# Cabinet_System_F.net
KiCad netlist of a schematic drawn in Altium Designer
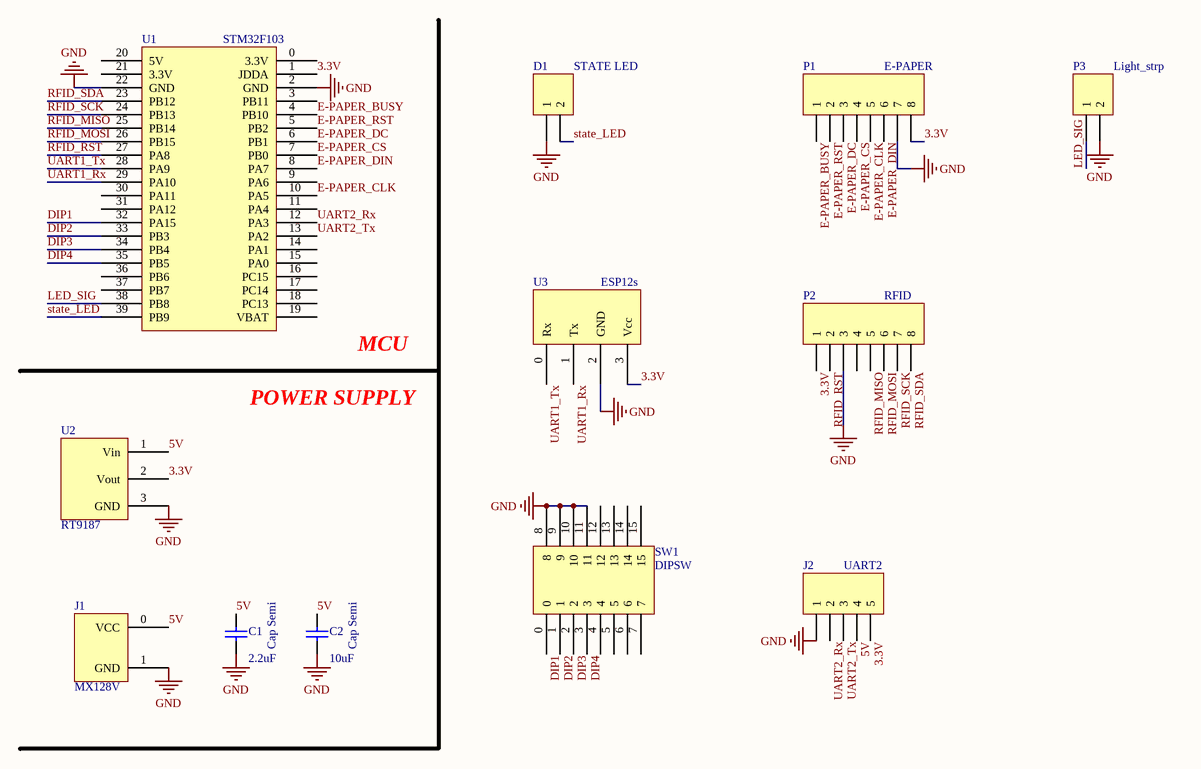
[diagram p0: Cabinet_System_F.SchDoc]

(export (version "E")
  (design (tool "Eeschema 10.0.6"))
  (components
    (comp (ref "C1")
      (value "Cap Semi")
      (footprint "1608[0603]")
      (description "Capacitor (Semiconductor SIM Model)")
      (fields (field (name "ALTIUM_VALUE") "2.2uF") (field (name "PUBLISHER") "Altium Limited"))
      (libsource (lib "Miscellaneous Devices") (part "Cap Semi"))
    )
    (comp (ref "C2")
      (value "Cap Semi")
      (footprint "1608[0603]")
      (description "Capacitor (Semiconductor SIM Model)")
      (fields (field (name "ALTIUM_VALUE") "10uF") (field (name "PUBLISHER") "Altium Limited"))
      (libsource (lib "Miscellaneous Devices") (part "Cap Semi"))
    )
    (comp (ref "D1")
      (value "STATE LED")
      (footprint "HDR1X2")
      (description "Header, 2-Pin")
      (fields (field (name "PUBLISHER") "Altium Limited"))
      (libsource (lib "Miscellaneous Connectors") (part "Header 2"))
    )
    (comp (ref "J1") (value "MX128V") (footprint "MX128V") (libsource (lib "cabinet_LIB") (part "MX128V")))
    (comp (ref "J2")
      (value "UART2")
      (footprint "HDR1X5")
      (description "Header, 5-Pin")
      (fields (field (name "PUBLISHER") "Altium Limited"))
      (libsource (lib "Miscellaneous Connectors") (part "Header 5"))
    )
    (comp (ref "P1")
      (value "E-PAPER")
      (footprint "HDR1X8")
      (description "Header, 8-Pin")
      (fields (field (name "PUBLISHER") "Altium Limited"))
      (libsource (lib "Miscellaneous Connectors") (part "Header 8"))
    )
    (comp (ref "P2")
      (value "RFID")
      (footprint "HDR1X8")
      (description "Header, 8-Pin")
      (fields (field (name "PUBLISHER") "Altium Limited"))
      (libsource (lib "Miscellaneous Connectors") (part "Header 8"))
    )
    (comp (ref "P3")
      (value "Light_strp")
      (footprint "HDR1X2")
      (description "Header, 2-Pin")
      (fields (field (name "PUBLISHER") "Altium Limited"))
      (libsource (lib "Miscellaneous Connectors") (part "Header 2"))
    )
    (comp (ref "SW1") (value "DIPSW") (footprint "DIPSW") (libsource (lib "cabinet_LIB") (part "DIPSW")))
    (comp (ref "U1")
      (value "STM32F103")
      (footprint "STM32F103")
      (libsource (lib "cabinet_LIB") (part "STM32F103"))
    )
    (comp (ref "U2") (value "RT9187") (footprint "RT9187") (libsource (lib "cabinet_LIB") (part "RT9187")))
    (comp (ref "U3") (value "ESP12s") (footprint "ESP12s") (libsource (lib "cabinet_LIB") (part "ESP12s")))
  )
  (nets
    (net (code "1") (name "/3.3V") (class "Default")
      (node (ref "J2") (pin "5") (pinfunction "5_5") (pintype "passive"))
      (node (ref "P1") (pin "8") (pinfunction "8_8") (pintype "passive"))
      (node (ref "P2") (pin "1") (pinfunction "1_1") (pintype "passive"))
      (node (ref "U1") (pin "1") (pinfunction "JDDA_1") (pintype "passive"))
      (node (ref "U2") (pin "2") (pinfunction "Vout_2") (pintype "passive"))
      (node (ref "U3") (pin "3") (pinfunction "Vcc_3") (pintype "passive"))
    )
    (net (code "2") (name "/5V") (class "Default")
      (node (ref "C1") (pin "2") (pinfunction "2_2") (pintype "passive"))
      (node (ref "C2") (pin "2") (pinfunction "2_2") (pintype "passive"))
      (node (ref "J1") (pin "0") (pinfunction "VCC_0") (pintype "passive"))
      (node (ref "J2") (pin "4") (pinfunction "4_4") (pintype "passive"))
      (node (ref "U2") (pin "1") (pinfunction "Vin_1") (pintype "passive"))
    )
    (net (code "3") (name "/DIP1") (class "Default")
      (node (ref "SW1") (pin "0") (pinfunction "0_0") (pintype "passive"))
      (node (ref "U1") (pin "32") (pinfunction "PA15_32") (pintype "passive"))
    )
    (net (code "4") (name "/DIP2") (class "Default")
      (node (ref "SW1") (pin "1") (pinfunction "1_1") (pintype "passive"))
      (node (ref "U1") (pin "33") (pinfunction "PB3_33") (pintype "passive"))
    )
    (net (code "5") (name "/DIP3") (class "Default")
      (node (ref "SW1") (pin "2") (pinfunction "2_2") (pintype "passive"))
      (node (ref "U1") (pin "34") (pinfunction "PB4_34") (pintype "passive"))
    )
    (net (code "6") (name "/DIP4") (class "Default")
      (node (ref "SW1") (pin "3") (pinfunction "3_3") (pintype "passive"))
      (node (ref "U1") (pin "35") (pinfunction "PB5_35") (pintype "passive"))
    )
    (net (code "7") (name "/E-PAPER_BUSY") (class "Default")
      (node (ref "P1") (pin "1") (pinfunction "1_1") (pintype "passive"))
      (node (ref "U1") (pin "4") (pinfunction "PB10_4") (pintype "passive"))
    )
    (net (code "8") (name "/E-PAPER_CLK") (class "Default")
      (node (ref "P1") (pin "5") (pinfunction "5_5") (pintype "passive"))
      (node (ref "U1") (pin "10") (pinfunction "PA5_10") (pintype "passive"))
    )
    (net (code "9") (name "/E-PAPER_CS") (class "Default")
      (node (ref "P1") (pin "4") (pinfunction "4_4") (pintype "passive"))
      (node (ref "U1") (pin "7") (pinfunction "PB0_7") (pintype "passive"))
    )
    (net (code "10") (name "/E-PAPER_DC") (class "Default")
      (node (ref "P1") (pin "3") (pinfunction "3_3") (pintype "passive"))
      (node (ref "U1") (pin "6") (pinfunction "PB1_6") (pintype "passive"))
    )
    (net (code "11") (name "/E-PAPER_DIN") (class "Default")
      (node (ref "P1") (pin "6") (pinfunction "6_6") (pintype "passive"))
      (node (ref "U1") (pin "8") (pinfunction "PA7_8") (pintype "passive"))
    )
    (net (code "12") (name "/E-PAPER_RST") (class "Default")
      (node (ref "P1") (pin "2") (pinfunction "2_2") (pintype "passive"))
      (node (ref "U1") (pin "5") (pinfunction "PB2_5") (pintype "passive"))
    )
    (net (code "13") (name "/LED_SIG") (class "Default")
      (node (ref "P3") (pin "1") (pinfunction "1_1") (pintype "passive"))
      (node (ref "U1") (pin "38") (pinfunction "PB8_38") (pintype "passive"))
    )
    (net (code "14") (name "/RFID_MISO") (class "Default")
      (node (ref "P2") (pin "5") (pinfunction "5_5") (pintype "passive"))
      (node (ref "U1") (pin "25") (pinfunction "PB14_25") (pintype "passive"))
    )
    (net (code "15") (name "/RFID_MOSI") (class "Default")
      (node (ref "P2") (pin "6") (pinfunction "6_6") (pintype "passive"))
      (node (ref "U1") (pin "26") (pinfunction "PB15_26") (pintype "passive"))
    )
    (net (code "16") (name "/RFID_RST") (class "Default")
      (node (ref "P2") (pin "2") (pinfunction "2_2") (pintype "passive"))
      (node (ref "U1") (pin "27") (pinfunction "PA8_27") (pintype "passive"))
    )
    (net (code "17") (name "/RFID_SCK") (class "Default")
      (node (ref "P2") (pin "7") (pinfunction "7_7") (pintype "passive"))
      (node (ref "U1") (pin "24") (pinfunction "PB13_24") (pintype "passive"))
    )
    (net (code "18") (name "/RFID_SDA") (class "Default")
      (node (ref "P2") (pin "8") (pinfunction "8_8") (pintype "passive"))
      (node (ref "U1") (pin "23") (pinfunction "PB12_23") (pintype "passive"))
    )
    (net (code "19") (name "/UART1_Rx") (class "Default")
      (node (ref "U1") (pin "29") (pinfunction "PA10_29") (pintype "passive"))
      (node (ref "U3") (pin "1") (pinfunction "Tx_1") (pintype "passive"))
    )
    (net (code "20") (name "/UART1_Tx") (class "Default")
      (node (ref "U1") (pin "28") (pinfunction "PA9_28") (pintype "passive"))
      (node (ref "U3") (pin "0") (pinfunction "Rx_0") (pintype "passive"))
    )
    (net (code "21") (name "/UART2_Rx") (class "Default")
      (node (ref "J2") (pin "2") (pinfunction "2_2") (pintype "passive"))
      (node (ref "U1") (pin "12") (pinfunction "PA3_12") (pintype "passive"))
    )
    (net (code "22") (name "/UART2_Tx") (class "Default")
      (node (ref "J2") (pin "3") (pinfunction "3_3") (pintype "passive"))
      (node (ref "U1") (pin "13") (pinfunction "PA2_13") (pintype "passive"))
    )
    (net (code "23") (name "/state_LED") (class "Default")
      (node (ref "D1") (pin "2") (pinfunction "2_2") (pintype "passive"))
      (node (ref "U1") (pin "39") (pinfunction "PB9_39") (pintype "passive"))
    )
    (net (code "24") (name "GND") (class "Default")
      (node (ref "C1") (pin "1") (pinfunction "1_1") (pintype "passive"))
      (node (ref "C2") (pin "1") (pinfunction "1_1") (pintype "passive"))
      (node (ref "D1") (pin "1") (pinfunction "1_1") (pintype "passive"))
      (node (ref "J1") (pin "1") (pinfunction "GND_1") (pintype "passive"))
      (node (ref "J2") (pin "1") (pinfunction "1_1") (pintype "passive"))
      (node (ref "P1") (pin "7") (pinfunction "7_7") (pintype "passive"))
      (node (ref "P2") (pin "3") (pinfunction "3_3") (pintype "passive"))
      (node (ref "P3") (pin "2") (pinfunction "2_2") (pintype "passive"))
      (node (ref "SW1") (pin "10") (pinfunction "10_10") (pintype "passive"))
      (node (ref "SW1") (pin "11") (pinfunction "11_11") (pintype "passive"))
      (node (ref "SW1") (pin "8") (pinfunction "8_8") (pintype "passive"))
      (node (ref "SW1") (pin "9") (pinfunction "9_9") (pintype "passive"))
      (node (ref "U1") (pin "2") (pinfunction "GND_2") (pintype "passive"))
      (node (ref "U1") (pin "22") (pinfunction "GND_22") (pintype "passive"))
      (node (ref "U2") (pin "3") (pinfunction "GND_3") (pintype "passive"))
      (node (ref "U3") (pin "2") (pinfunction "GND_2") (pintype "passive"))
    )
    (net (code "25") (name "unconnected-(P2-Pad4)") (class "Default")
      (node (ref "P2") (pin "4") (pinfunction "4_4") (pintype "passive"))
    )
    (net (code "26") (name "unconnected-(SW1-Pad4)") (class "Default")
      (node (ref "SW1") (pin "4") (pinfunction "4_4") (pintype "passive"))
    )
    (net (code "27") (name "unconnected-(SW1-Pad5)") (class "Default")
      (node (ref "SW1") (pin "5") (pinfunction "5_5") (pintype "passive"))
    )
    (net (code "28") (name "unconnected-(SW1-Pad6)") (class "Default")
      (node (ref "SW1") (pin "6") (pinfunction "6_6") (pintype "passive"))
    )
    (net (code "29") (name "unconnected-(SW1-Pad7)") (class "Default")
      (node (ref "SW1") (pin "7") (pinfunction "7_7") (pintype "passive"))
    )
    (net (code "30") (name "unconnected-(SW1-Pad12)") (class "Default")
      (node (ref "SW1") (pin "12") (pinfunction "12_12") (pintype "passive"))
    )
    (net (code "31") (name "unconnected-(SW1-Pad13)") (class "Default")
      (node (ref "SW1") (pin "13") (pinfunction "13_13") (pintype "passive"))
    )
    (net (code "32") (name "unconnected-(SW1-Pad14)") (class "Default")
      (node (ref "SW1") (pin "14") (pinfunction "14_14") (pintype "passive"))
    )
    (net (code "33") (name "unconnected-(SW1-Pad15)") (class "Default")
      (node (ref "SW1") (pin "15") (pinfunction "15_15") (pintype "passive"))
    )
    (net (code "34") (name "unconnected-(U1-3.3V-Pad0)") (class "Default")
      (node (ref "U1") (pin "0") (pinfunction "3.3V_0") (pintype "passive"))
    )
    (net (code "35") (name "unconnected-(U1-3.3V-Pad21)") (class "Default")
      (node (ref "U1") (pin "21") (pinfunction "3.3V_21") (pintype "passive"))
    )
    (net (code "36") (name "unconnected-(U1-5V-Pad20)") (class "Default")
      (node (ref "U1") (pin "20") (pinfunction "5V_20") (pintype "passive"))
    )
    (net (code "37") (name "unconnected-(U1-PA0-Pad15)") (class "Default")
      (node (ref "U1") (pin "15") (pinfunction "PA0_15") (pintype "passive"))
    )
    (net (code "38") (name "unconnected-(U1-PA1-Pad14)") (class "Default")
      (node (ref "U1") (pin "14") (pinfunction "PA1_14") (pintype "passive"))
    )
    (net (code "39") (name "unconnected-(U1-PA4-Pad11)") (class "Default")
      (node (ref "U1") (pin "11") (pinfunction "PA4_11") (pintype "passive"))
    )
    (net (code "40") (name "unconnected-(U1-PA6-Pad9)") (class "Default")
      (node (ref "U1") (pin "9") (pinfunction "PA6_9") (pintype "passive"))
    )
    (net (code "41") (name "unconnected-(U1-PA11-Pad30)") (class "Default")
      (node (ref "U1") (pin "30") (pinfunction "PA11_30") (pintype "passive"))
    )
    (net (code "42") (name "unconnected-(U1-PA12-Pad31)") (class "Default")
      (node (ref "U1") (pin "31") (pinfunction "PA12_31") (pintype "passive"))
    )
    (net (code "43") (name "unconnected-(U1-PB6-Pad36)") (class "Default")
      (node (ref "U1") (pin "36") (pinfunction "PB6_36") (pintype "passive"))
    )
    (net (code "44") (name "unconnected-(U1-PB7-Pad37)") (class "Default")
      (node (ref "U1") (pin "37") (pinfunction "PB7_37") (pintype "passive"))
    )
    (net (code "45") (name "unconnected-(U1-PB11-Pad3)") (class "Default")
      (node (ref "U1") (pin "3") (pinfunction "PB11_3") (pintype "passive"))
    )
    (net (code "46") (name "unconnected-(U1-PC13-Pad18)") (class "Default")
      (node (ref "U1") (pin "18") (pinfunction "PC13_18") (pintype "passive"))
    )
    (net (code "47") (name "unconnected-(U1-PC14-Pad17)") (class "Default")
      (node (ref "U1") (pin "17") (pinfunction "PC14_17") (pintype "passive"))
    )
    (net (code "48") (name "unconnected-(U1-PC15-Pad16)") (class "Default")
      (node (ref "U1") (pin "16") (pinfunction "PC15_16") (pintype "passive"))
    )
    (net (code "49") (name "unconnected-(U1-VBAT-Pad19)") (class "Default")
      (node (ref "U1") (pin "19") (pinfunction "VBAT_19") (pintype "passive"))
    )
  )
)
